# ai_breakout_bme2802.net
KiCad netlist of a schematic drawn in EAGLE
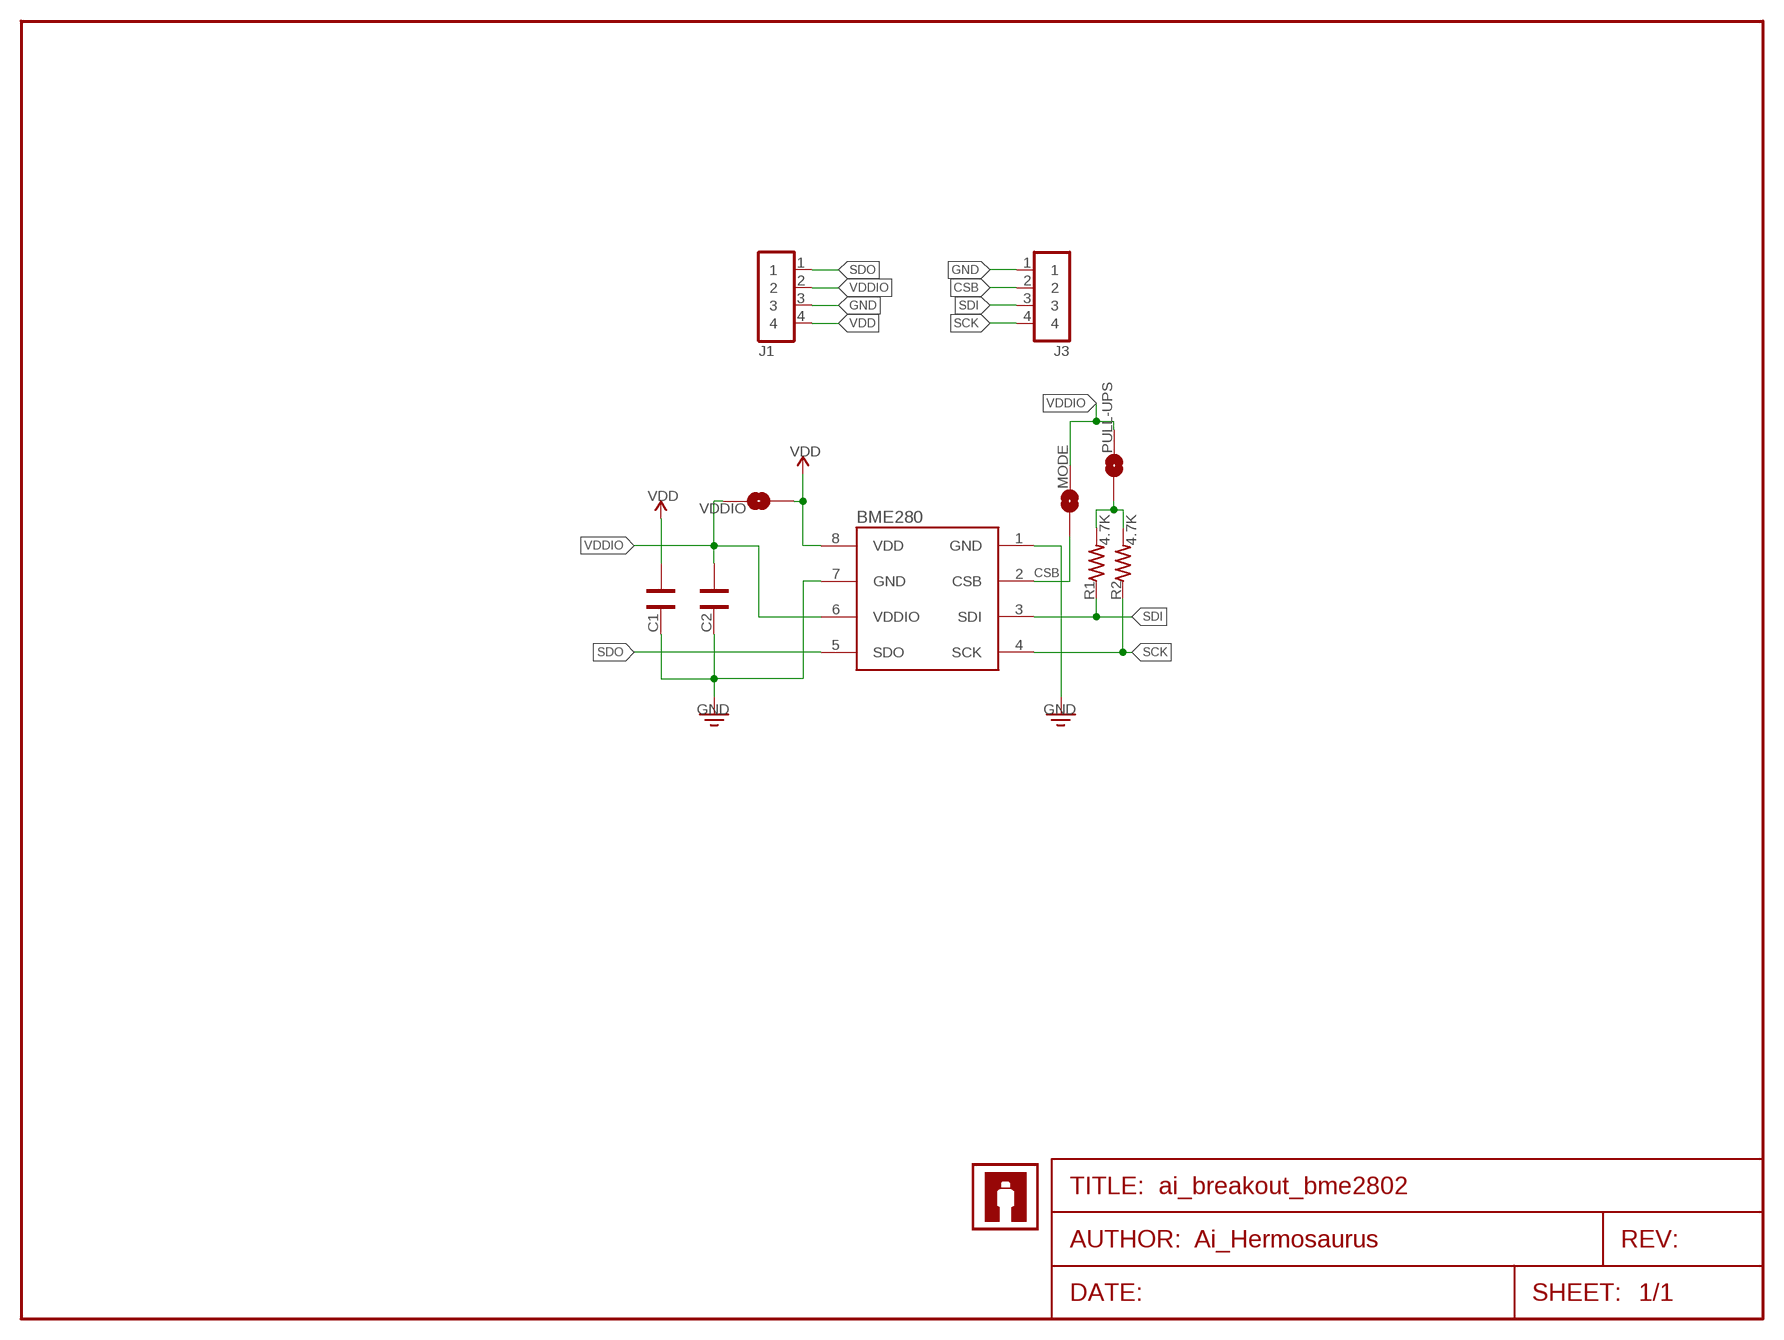
[diagram p0: schematic, sheet 1]

(export (version "E")
  (design (tool "Eeschema 10.0.6"))
  (components
    (comp (ref "C1")
      (value "CAP0603")
      (footprint "eagle-import:CAP-0603")
      (libsource (lib "eagle-import") (part "CAP0603"))
    )
    (comp (ref "C2")
      (value "CAP0603")
      (footprint "eagle-import:CAP-0603")
      (libsource (lib "eagle-import") (part "CAP0603"))
    )
    (comp (ref "J1")
      (value "1X04NOFIRST")
      (footprint "eagle-import:1X04-NOFIRST")
      (libsource (lib "eagle-import") (part "1X04NOFIRST"))
    )
    (comp (ref "J3")
      (value "1X04")
      (footprint "eagle-import:1X04")
      (libsource (lib "eagle-import") (part "1X04"))
    )
    (comp (ref "MODE")
      (value "1X02-SJ-NO")
      (footprint "eagle-import:1X02-SJ-NO")
      (libsource (lib "eagle-import") (part "1X02-SJ-NO"))
    )
    (comp (ref "PULL-UPS")
      (value "1X02-SJ-NO")
      (footprint "eagle-import:1X02-SJ-NO")
      (libsource (lib "eagle-import") (part "1X02-SJ-NO"))
    )
    (comp (ref "R1")
      (value "4.7K")
      (footprint "eagle-import:RES-0603")
      (libsource (lib "eagle-import") (part "RES0603"))
    )
    (comp (ref "R2")
      (value "4.7K")
      (footprint "eagle-import:RES-0603")
      (libsource (lib "eagle-import") (part "RES0603"))
    )
    (comp (ref "U$2")
      (value "AI-LOGOXS")
      (footprint "eagle-import:AI-LOGO-XS")
      (libsource (lib "eagle-import") (part "AI-LOGOXS"))
    )
    (comp (ref "U1")
      (value "BME280")
      (footprint "eagle-import:BME280")
      (libsource (lib "eagle-import") (part "BME280"))
    )
    (comp (ref "VDDIO")
      (value "1X02-SJ-NO")
      (footprint "eagle-import:1X02-SJ-NO")
      (libsource (lib "eagle-import") (part "1X02-SJ-NO"))
    )
  )
  (nets
    (net (code "1") (name "CSB") (class "Default")
      (node (ref "J3") (pin "2") (pinfunction "2_2") (pintype "bidirectional"))
      (node (ref "MODE") (pin "1") (pinfunction "1_1") (pintype "passive"))
      (node (ref "U1") (pin "2") (pinfunction "CSB_2") (pintype "power_in"))
    )
    (net (code "2") (name "GND") (class "Default")
      (node (ref "C1") (pin "2") (pinfunction "2_2") (pintype "passive"))
      (node (ref "C2") (pin "2") (pinfunction "2_2") (pintype "passive"))
      (node (ref "J1") (pin "3") (pinfunction "3_3") (pintype "bidirectional"))
      (node (ref "J3") (pin "1") (pinfunction "1_1") (pintype "bidirectional"))
      (node (ref "U1") (pin "1") (pinfunction "GND_1") (pintype "power_in"))
      (node (ref "U1") (pin "7") (pinfunction "GND_7") (pintype "power_in"))
    )
    (net (code "3") (name "Net-(PULL-UPS-Pad1)") (class "Default")
      (node (ref "PULL-UPS") (pin "1") (pinfunction "1_1") (pintype "passive"))
      (node (ref "R1") (pin "2") (pinfunction "2_2") (pintype "passive"))
      (node (ref "R2") (pin "2") (pinfunction "2_2") (pintype "passive"))
    )
    (net (code "4") (name "SCK") (class "Default")
      (node (ref "J3") (pin "4") (pinfunction "4_4") (pintype "bidirectional"))
      (node (ref "R2") (pin "1") (pinfunction "1_1") (pintype "passive"))
      (node (ref "U1") (pin "4") (pinfunction "SCK_4") (pintype "input"))
    )
    (net (code "5") (name "SDI") (class "Default")
      (node (ref "J3") (pin "3") (pinfunction "3_3") (pintype "bidirectional"))
      (node (ref "R1") (pin "1") (pinfunction "1_1") (pintype "passive"))
      (node (ref "U1") (pin "3") (pinfunction "SDI_3") (pintype "input"))
    )
    (net (code "6") (name "SDO") (class "Default")
      (node (ref "J1") (pin "1") (pinfunction "1_1") (pintype "bidirectional"))
      (node (ref "U1") (pin "5") (pinfunction "SDO_5") (pintype "bidirectional"))
    )
    (net (code "7") (name "VDD") (class "Default")
      (node (ref "C1") (pin "1") (pinfunction "1_1") (pintype "passive"))
      (node (ref "J1") (pin "4") (pinfunction "4_4") (pintype "bidirectional"))
      (node (ref "U1") (pin "8") (pinfunction "VDD_8") (pintype "power_in"))
      (node (ref "VDDIO") (pin "1") (pinfunction "1_1") (pintype "passive"))
    )
    (net (code "8") (name "VDDIO") (class "Default")
      (node (ref "C2") (pin "1") (pinfunction "1_1") (pintype "passive"))
      (node (ref "J1") (pin "2") (pinfunction "2_2") (pintype "bidirectional"))
      (node (ref "MODE") (pin "2") (pinfunction "2_2") (pintype "passive"))
      (node (ref "PULL-UPS") (pin "2") (pinfunction "2_2") (pintype "passive"))
      (node (ref "U1") (pin "6") (pinfunction "VDDIO_6") (pintype "power_in"))
      (node (ref "VDDIO") (pin "2") (pinfunction "2_2") (pintype "passive"))
    )
  )
)
